# LCD_Disp_AIR.net
KiCad netlist of a schematic drawn in EAGLE
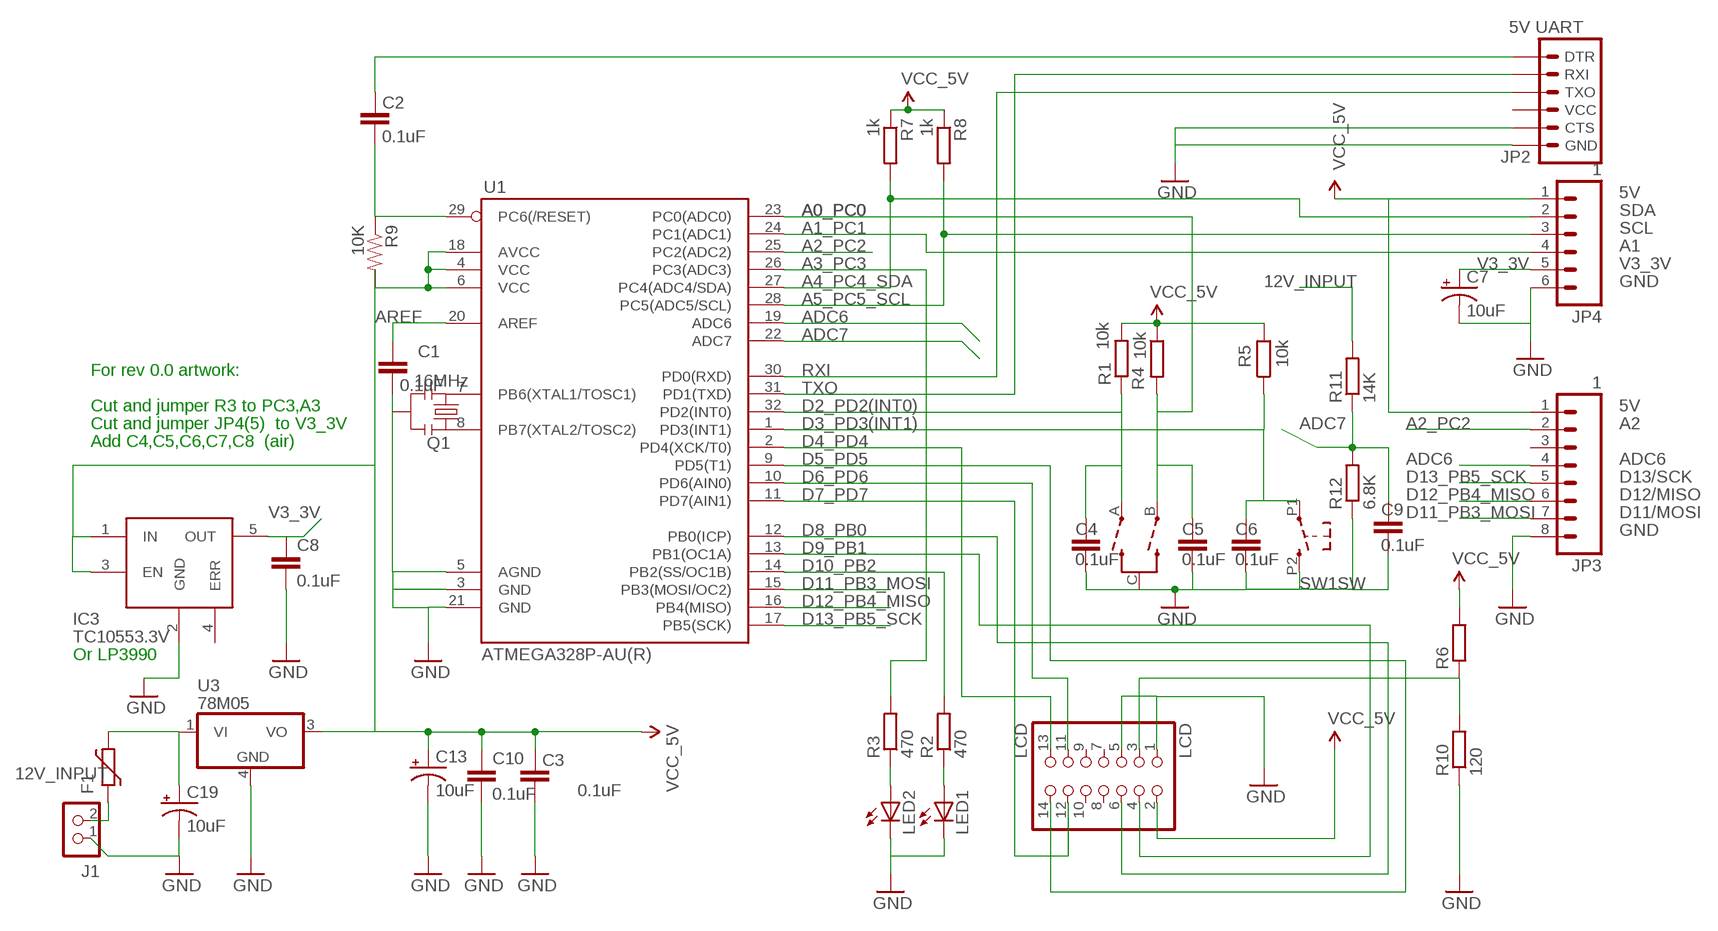
[diagram p0: schematic, sheet 1]

(export (version "E")
  (design (tool "Eeschema 10.0.6"))
  (components
    (comp (ref "C1")
      (value "0.1uF")
      (footprint "eagle-import:0805")
      (libsource (lib "eagle-import") (part "CAP0805"))
    )
    (comp (ref "C2")
      (value "0.1uF")
      (footprint "eagle-import:0805")
      (libsource (lib "eagle-import") (part "CAP0805"))
    )
    (comp (ref "C3")
      (value "0.1uF")
      (footprint "eagle-import:0805")
      (libsource (lib "eagle-import") (part "CAP0805"))
    )
    (comp (ref "C4")
      (value "0.1uF")
      (footprint "eagle-import:0805")
      (libsource (lib "eagle-import") (part "CAP0805"))
    )
    (comp (ref "C5")
      (value "0.1uF")
      (footprint "eagle-import:0805")
      (libsource (lib "eagle-import") (part "CAP0805"))
    )
    (comp (ref "C6")
      (value "0.1uF")
      (footprint "eagle-import:0805")
      (libsource (lib "eagle-import") (part "CAP0805"))
    )
    (comp (ref "C7")
      (value "10uF")
      (footprint "eagle-import:EIA3216")
      (libsource (lib "eagle-import") (part "CAP_POL1206"))
    )
    (comp (ref "C8")
      (value "0.1uF")
      (footprint "eagle-import:0805")
      (libsource (lib "eagle-import") (part "CAP0805"))
    )
    (comp (ref "C9")
      (value "0.1uF")
      (footprint "eagle-import:0805")
      (libsource (lib "eagle-import") (part "CAP0805"))
    )
    (comp (ref "C10")
      (value "0.1uF")
      (footprint "eagle-import:0805")
      (libsource (lib "eagle-import") (part "CAP0805"))
    )
    (comp (ref "C13")
      (value "10uF")
      (footprint "eagle-import:EIA3216")
      (libsource (lib "eagle-import") (part "CAP_POL1206"))
    )
    (comp (ref "C19")
      (value "10uF")
      (footprint "eagle-import:EIA7343")
      (libsource (lib "eagle-import") (part "CAP_POL7343"))
    )
    (comp (ref "F1")
      (value "FUSE_PTC-0805")
      (footprint "eagle-import:PTC0805")
      (libsource (lib "eagle-import") (part "FUSE_PTC-0805"))
    )
    (comp (ref "IC3")
      (value "TC10553.3V")
      (footprint "eagle-import:SOT23-5")
      (libsource (lib "eagle-import") (part "TC10553.3V"))
    )
    (comp (ref "J1")
      (value "12V input")
      (footprint "eagle-import:M1X2")
      (libsource (lib "eagle-import") (part "CON_HEADER_1X02-PTH"))
    )
    (comp (ref "JP2")
      (value "5V UART")
      (footprint "eagle-import:1X06")
      (libsource (lib "eagle-import") (part "ARDUINO_SERIAL_PROGRAMPTH"))
    )
    (comp (ref "JP3")
      (value "1")
      (footprint "eagle-import:1X08")
      (libsource (lib "eagle-import") (part "M081X08"))
    )
    (comp (ref "JP4")
      (value "1")
      (footprint "eagle-import:1X06")
      (libsource (lib "eagle-import") (part "M06SIP"))
    )
    (comp (ref "LCD")
      (value "LCD")
      (footprint "eagle-import:2X07")
      (libsource (lib "eagle-import") (part "PINHD-2X7"))
    )
    (comp (ref "LED1")
      (value "LED-5MM")
      (footprint "eagle-import:LED-5MM")
      (libsource (lib "eagle-import") (part "LED-5MM"))
    )
    (comp (ref "LED2")
      (value "LED-5MM")
      (footprint "eagle-import:LED-5MM")
      (libsource (lib "eagle-import") (part "LED-5MM"))
    )
    (comp (ref "Q1")
      (value "16MHz")
      (footprint "eagle-import:RESONATOR-SMD")
      (libsource (lib "eagle-import") (part "RESONATORSMD"))
    )
    (comp (ref "R1")
      (value "10k")
      (footprint "eagle-import:R603")
      (libsource (lib "eagle-import") (part "RESISTOR-0603"))
    )
    (comp (ref "R2")
      (value "470")
      (footprint "eagle-import:R603")
      (libsource (lib "eagle-import") (part "RESISTOR-0603"))
    )
    (comp (ref "R3")
      (value "470")
      (footprint "eagle-import:R603")
      (libsource (lib "eagle-import") (part "RESISTOR-0603"))
    )
    (comp (ref "R4")
      (value "10k")
      (footprint "eagle-import:R603")
      (libsource (lib "eagle-import") (part "RESISTOR-0603"))
    )
    (comp (ref "R5")
      (value "10k")
      (footprint "eagle-import:R603")
      (libsource (lib "eagle-import") (part "RESISTOR-0603"))
    )
    (comp (ref "R6")
      (value "RESISTOR-0603")
      (footprint "eagle-import:R603")
      (libsource (lib "eagle-import") (part "RESISTOR-0603"))
    )
    (comp (ref "R7")
      (value "1k")
      (footprint "eagle-import:R603")
      (libsource (lib "eagle-import") (part "RESISTOR-0603"))
    )
    (comp (ref "R8")
      (value "1k")
      (footprint "eagle-import:R603")
      (libsource (lib "eagle-import") (part "RESISTOR-0603"))
    )
    (comp (ref "R9")
      (value "10K")
      (footprint "eagle-import:0603")
      (libsource (lib "eagle-import") (part "RESISTOR0603"))
    )
    (comp (ref "R10")
      (value "120")
      (footprint "eagle-import:R603")
      (libsource (lib "eagle-import") (part "RESISTOR-0603"))
    )
    (comp (ref "R11")
      (value "14K")
      (footprint "eagle-import:R603")
      (libsource (lib "eagle-import") (part "RESISTOR-0603"))
    )
    (comp (ref "R12")
      (value "6.8K")
      (footprint "eagle-import:R603")
      (libsource (lib "eagle-import") (part "RESISTOR-0603"))
    )
    (comp (ref "SW1")
      (value "ENCODER_SW1-PEC12")
      (footprint "eagle-import:PEC12_INCREMENTAL_ENCODER")
      (libsource (lib "eagle-import") (part "ENCODER_SW1-PEC12"))
    )
    (comp (ref "U1")
      (value "ATMEGA328P-AU(R)")
      (footprint "eagle-import:TQFP32-08")
      (libsource (lib "eagle-import") (part "ATMEGA168"))
    )
    (comp (ref "U3")
      (value "78M05")
      (footprint "eagle-import:DPACK")
      (libsource (lib "eagle-import") (part "78MXXL"))
    )
  )
  (nets
    (net (code "1") (name "/12V_INPUT") (class "Default")
      (node (ref "C19") (pin "A") (pinfunction "+_A") (pintype "passive"))
      (node (ref "F1") (pin "2") (pinfunction "2_2") (pintype "passive"))
      (node (ref "R11") (pin "2") (pinfunction "2_2") (pintype "passive"))
      (node (ref "U3") (pin "1") (pinfunction "VI_1") (pintype "input"))
    )
    (net (code "2") (name "/A0_PC0") (class "Default")
      (node (ref "C5") (pin "2") (pinfunction "2_2") (pintype "passive"))
      (node (ref "R4") (pin "2") (pinfunction "2_2") (pintype "passive"))
      (node (ref "SW1") (pin "B") (pinfunction "B_B") (pintype "passive"))
      (node (ref "U1") (pin "23") (pinfunction "PC0(ADC0)_23") (pintype "bidirectional"))
    )
    (net (code "3") (name "/A1_PC1") (class "Default")
      (node (ref "JP4") (pin "4") (pinfunction "4_4") (pintype "passive"))
      (node (ref "U1") (pin "24") (pinfunction "PC1(ADC1)_24") (pintype "bidirectional"))
    )
    (net (code "4") (name "/A2_PC2") (class "Default")
      (node (ref "JP3") (pin "2") (pinfunction "2_2") (pintype "passive"))
      (node (ref "U1") (pin "25") (pinfunction "PC2(ADC2)_25") (pintype "bidirectional"))
    )
    (net (code "5") (name "/A3_PC3") (class "Default")
      (node (ref "R3") (pin "2") (pinfunction "2_2") (pintype "passive"))
      (node (ref "U1") (pin "26") (pinfunction "PC3(ADC3)_26") (pintype "bidirectional"))
    )
    (net (code "6") (name "/A4_PC4_SDA") (class "Default")
      (node (ref "JP4") (pin "2") (pinfunction "2_2") (pintype "passive"))
      (node (ref "R7") (pin "2") (pinfunction "2_2") (pintype "passive"))
      (node (ref "U1") (pin "27") (pinfunction "PC4(ADC4/SDA)_27") (pintype "bidirectional"))
    )
    (net (code "7") (name "/A5_PC5_SCL") (class "Default")
      (node (ref "JP4") (pin "3") (pinfunction "3_3") (pintype "passive"))
      (node (ref "R8") (pin "2") (pinfunction "2_2") (pintype "passive"))
      (node (ref "U1") (pin "28") (pinfunction "PC5(ADC5/SCL)_28") (pintype "bidirectional"))
    )
    (net (code "8") (name "/ADC6") (class "Default")
      (node (ref "JP3") (pin "4") (pinfunction "4_4") (pintype "passive"))
      (node (ref "U1") (pin "19") (pinfunction "ADC6_19") (pintype "bidirectional"))
    )
    (net (code "9") (name "/ADC7") (class "Default")
      (node (ref "C9") (pin "1") (pinfunction "1_1") (pintype "passive"))
      (node (ref "R11") (pin "1") (pinfunction "1_1") (pintype "passive"))
      (node (ref "R12") (pin "2") (pinfunction "2_2") (pintype "passive"))
      (node (ref "U1") (pin "22") (pinfunction "ADC7_22") (pintype "bidirectional"))
    )
    (net (code "10") (name "/AREF") (class "Default")
      (node (ref "C1") (pin "2") (pinfunction "2_2") (pintype "passive"))
      (node (ref "U1") (pin "20") (pinfunction "AREF_20") (pintype "bidirectional"))
    )
    (net (code "11") (name "/D2_PD2(INT0)") (class "Default")
      (node (ref "C4") (pin "2") (pinfunction "2_2") (pintype "passive"))
      (node (ref "R1") (pin "1") (pinfunction "1_1") (pintype "passive"))
      (node (ref "SW1") (pin "A") (pinfunction "A_A") (pintype "passive"))
      (node (ref "U1") (pin "32") (pinfunction "PD2(INT0)_32") (pintype "bidirectional"))
    )
    (net (code "12") (name "/D3_PD3(INT1)") (class "Default")
      (node (ref "C6") (pin "2") (pinfunction "2_2") (pintype "passive"))
      (node (ref "R5") (pin "1") (pinfunction "1_1") (pintype "passive"))
      (node (ref "SW1") (pin "P1") (pinfunction "1_P1") (pintype "passive"))
      (node (ref "U1") (pin "1") (pinfunction "PD3(INT1)_1") (pintype "bidirectional"))
    )
    (net (code "13") (name "/D4_PD4") (class "Default")
      (node (ref "LCD") (pin "13") (pinfunction "13_13") (pintype "passive"))
      (node (ref "U1") (pin "2") (pinfunction "PD4(XCK/T0)_2") (pintype "bidirectional"))
    )
    (net (code "14") (name "/D5_PD5") (class "Default")
      (node (ref "LCD") (pin "14") (pinfunction "14_14") (pintype "passive"))
      (node (ref "U1") (pin "9") (pinfunction "PD5(T1)_9") (pintype "bidirectional"))
    )
    (net (code "15") (name "/D6_PD6") (class "Default")
      (node (ref "LCD") (pin "11") (pinfunction "11_11") (pintype "passive"))
      (node (ref "U1") (pin "10") (pinfunction "PD6(AIN0)_10") (pintype "bidirectional"))
    )
    (net (code "16") (name "/D7_PD7") (class "Default")
      (node (ref "LCD") (pin "12") (pinfunction "12_12") (pintype "passive"))
      (node (ref "U1") (pin "11") (pinfunction "PD7(AIN1)_11") (pintype "bidirectional"))
    )
    (net (code "17") (name "/D8_PB0") (class "Default")
      (node (ref "LCD") (pin "6") (pinfunction "6_6") (pintype "passive"))
      (node (ref "U1") (pin "12") (pinfunction "PB0(ICP)_12") (pintype "bidirectional"))
    )
    (net (code "18") (name "/D9_PB1") (class "Default")
      (node (ref "LCD") (pin "4") (pinfunction "4_4") (pintype "passive"))
      (node (ref "U1") (pin "13") (pinfunction "PB1(OC1A)_13") (pintype "bidirectional"))
    )
    (net (code "19") (name "/D10_PB2") (class "Default")
      (node (ref "R2") (pin "2") (pinfunction "2_2") (pintype "passive"))
      (node (ref "U1") (pin "14") (pinfunction "PB2(SS/OC1B)_14") (pintype "bidirectional"))
    )
    (net (code "20") (name "/D11_PB3_MOSI") (class "Default")
      (node (ref "JP3") (pin "7") (pinfunction "7_7") (pintype "passive"))
      (node (ref "U1") (pin "15") (pinfunction "PB3(MOSI/OC2)_15") (pintype "bidirectional"))
    )
    (net (code "21") (name "/D12_PB4_MISO") (class "Default")
      (node (ref "JP3") (pin "6") (pinfunction "6_6") (pintype "passive"))
      (node (ref "U1") (pin "16") (pinfunction "PB4(MISO)_16") (pintype "bidirectional"))
    )
    (net (code "22") (name "/D13_PB5_SCK") (class "Default")
      (node (ref "JP3") (pin "5") (pinfunction "5_5") (pintype "passive"))
      (node (ref "U1") (pin "17") (pinfunction "PB5(SCK)_17") (pintype "bidirectional"))
    )
    (net (code "23") (name "/RXI") (class "Default")
      (node (ref "JP2") (pin "3") (pinfunction "TXO_3") (pintype "passive"))
      (node (ref "U1") (pin "30") (pinfunction "PD0(RXD)_30") (pintype "bidirectional"))
    )
    (net (code "24") (name "/TXO") (class "Default")
      (node (ref "JP2") (pin "2") (pinfunction "RXI_2") (pintype "passive"))
      (node (ref "U1") (pin "31") (pinfunction "PD1(TXD)_31") (pintype "bidirectional"))
    )
    (net (code "25") (name "/V3_3V") (class "Default")
      (node (ref "C7") (pin "A") (pinfunction "+_A") (pintype "passive"))
      (node (ref "C8") (pin "1") (pinfunction "1_1") (pintype "passive"))
      (node (ref "IC3") (pin "5") (pinfunction "OUT_5") (pintype "power_in"))
      (node (ref "JP4") (pin "5") (pinfunction "5_5") (pintype "passive"))
    )
    (net (code "26") (name "GND") (class "Default")
      (node (ref "C1") (pin "1") (pinfunction "1_1") (pintype "passive"))
      (node (ref "C10") (pin "2") (pinfunction "2_2") (pintype "passive"))
      (node (ref "C13") (pin "C") (pinfunction "-_C") (pintype "passive"))
      (node (ref "C19") (pin "C") (pinfunction "-_C") (pintype "passive"))
      (node (ref "C3") (pin "1") (pinfunction "1_1") (pintype "passive"))
      (node (ref "C4") (pin "1") (pinfunction "1_1") (pintype "passive"))
      (node (ref "C5") (pin "1") (pinfunction "1_1") (pintype "passive"))
      (node (ref "C6") (pin "1") (pinfunction "1_1") (pintype "passive"))
      (node (ref "C7") (pin "C") (pinfunction "-_C") (pintype "passive"))
      (node (ref "C8") (pin "2") (pinfunction "2_2") (pintype "passive"))
      (node (ref "C9") (pin "2") (pinfunction "2_2") (pintype "passive"))
      (node (ref "IC3") (pin "2") (pinfunction "GND_2") (pintype "power_in"))
      (node (ref "J1") (pin "1") (pinfunction "1_1") (pintype "passive"))
      (node (ref "JP2") (pin "5") (pinfunction "CTS_5") (pintype "passive"))
      (node (ref "JP2") (pin "6") (pinfunction "GND_6") (pintype "passive"))
      (node (ref "JP3") (pin "8") (pinfunction "8_8") (pintype "passive"))
      (node (ref "JP4") (pin "6") (pinfunction "6_6") (pintype "passive"))
      (node (ref "LCD") (pin "1") (pinfunction "1_1") (pintype "passive"))
      (node (ref "LCD") (pin "5") (pinfunction "5_5") (pintype "passive"))
      (node (ref "LED1") (pin "K") (pinfunction "C_K") (pintype "passive"))
      (node (ref "LED2") (pin "K") (pinfunction "C_K") (pintype "passive"))
      (node (ref "Q1") (pin "2") (pinfunction "2_2") (pintype "passive"))
      (node (ref "R10") (pin "1") (pinfunction "1_1") (pintype "passive"))
      (node (ref "R12") (pin "1") (pinfunction "1_1") (pintype "passive"))
      (node (ref "SW1") (pin "C") (pinfunction "C_C") (pintype "passive"))
      (node (ref "SW1") (pin "P2") (pinfunction "2_P2") (pintype "passive"))
      (node (ref "U1") (pin "21") (pinfunction "GND_21") (pintype "bidirectional"))
      (node (ref "U1") (pin "3") (pinfunction "GND_3") (pintype "bidirectional"))
      (node (ref "U1") (pin "5") (pinfunction "AGND_5") (pintype "bidirectional"))
      (node (ref "U3") (pin "4") (pinfunction "GND_4") (pintype "passive"))
    )
    (net (code "27") (name "Net-(F1-Pad1)") (class "Default")
      (node (ref "F1") (pin "1") (pinfunction "1_1") (pintype "passive"))
      (node (ref "J1") (pin "2") (pinfunction "2_2") (pintype "passive"))
    )
    (net (code "28") (name "Net-(JP2-DTR)") (class "Default")
      (node (ref "C2") (pin "2") (pinfunction "2_2") (pintype "passive"))
      (node (ref "JP2") (pin "1") (pinfunction "DTR_1") (pintype "passive"))
    )
    (net (code "29") (name "Net-(LCD-Pad3)") (class "Default")
      (node (ref "LCD") (pin "3") (pinfunction "3_3") (pintype "passive"))
      (node (ref "R10") (pin "2") (pinfunction "2_2") (pintype "passive"))
      (node (ref "R6") (pin "1") (pinfunction "1_1") (pintype "passive"))
    )
    (net (code "30") (name "Net-(LED1-PadA)") (class "Default")
      (node (ref "LED1") (pin "A") (pinfunction "A_A") (pintype "passive"))
      (node (ref "R2") (pin "1") (pinfunction "1_1") (pintype "passive"))
    )
    (net (code "31") (name "Net-(LED2-PadA)") (class "Default")
      (node (ref "LED2") (pin "A") (pinfunction "A_A") (pintype "passive"))
      (node (ref "R3") (pin "1") (pinfunction "1_1") (pintype "passive"))
    )
    (net (code "32") (name "Net-(U1-PB6(XTAL1{slash}TOSC1))") (class "Default")
      (node (ref "Q1") (pin "3") (pinfunction "3_3") (pintype "passive"))
      (node (ref "U1") (pin "7") (pinfunction "PB6(XTAL1/TOSC1)_7") (pintype "bidirectional"))
    )
    (net (code "33") (name "Net-(U1-PB7(XTAL2{slash}TOSC2))") (class "Default")
      (node (ref "Q1") (pin "1") (pinfunction "1_1") (pintype "passive"))
      (node (ref "U1") (pin "8") (pinfunction "PB7(XTAL2/TOSC2)_8") (pintype "bidirectional"))
    )
    (net (code "34") (name "Net-(U1-PC6({slash}RESET))") (class "Default")
      (node (ref "C2") (pin "1") (pinfunction "1_1") (pintype "passive"))
      (node (ref "R9") (pin "1") (pinfunction "1_1") (pintype "passive"))
      (node (ref "U1") (pin "29") (pinfunction "PC6(/RESET)_29") (pintype "bidirectional"))
    )
    (net (code "35") (name "VCC_5V") (class "Default")
      (node (ref "C10") (pin "1") (pinfunction "1_1") (pintype "passive"))
      (node (ref "C13") (pin "A") (pinfunction "+_A") (pintype "passive"))
      (node (ref "C3") (pin "2") (pinfunction "2_2") (pintype "passive"))
      (node (ref "IC3") (pin "1") (pinfunction "IN_1") (pintype "power_in"))
      (node (ref "IC3") (pin "3") (pinfunction "EN_3") (pintype "input"))
      (node (ref "JP3") (pin "1") (pinfunction "1_1") (pintype "passive"))
      (node (ref "JP4") (pin "1") (pinfunction "1_1") (pintype "passive"))
      (node (ref "LCD") (pin "2") (pinfunction "2_2") (pintype "passive"))
      (node (ref "R1") (pin "2") (pinfunction "2_2") (pintype "passive"))
      (node (ref "R4") (pin "1") (pinfunction "1_1") (pintype "passive"))
      (node (ref "R5") (pin "2") (pinfunction "2_2") (pintype "passive"))
      (node (ref "R6") (pin "2") (pinfunction "2_2") (pintype "passive"))
      (node (ref "R7") (pin "1") (pinfunction "1_1") (pintype "passive"))
      (node (ref "R8") (pin "1") (pinfunction "1_1") (pintype "passive"))
      (node (ref "R9") (pin "2") (pinfunction "2_2") (pintype "passive"))
      (node (ref "U1") (pin "18") (pinfunction "AVCC_18") (pintype "bidirectional"))
      (node (ref "U1") (pin "4") (pinfunction "VCC_4") (pintype "bidirectional"))
      (node (ref "U1") (pin "6") (pinfunction "VCC_6") (pintype "bidirectional"))
      (node (ref "U3") (pin "3") (pinfunction "VO_3") (pintype "passive"))
    )
    (net (code "36") (name "unconnected-(IC3-ERR-Pad4)") (class "Default")
      (node (ref "IC3") (pin "4") (pinfunction "ERR_4") (pintype "output"))
    )
    (net (code "37") (name "unconnected-(JP2-VCC-Pad4)") (class "Default")
      (node (ref "JP2") (pin "4") (pinfunction "VCC_4") (pintype "passive"))
    )
    (net (code "38") (name "unconnected-(JP3-Pad3)") (class "Default")
      (node (ref "JP3") (pin "3") (pinfunction "3_3") (pintype "passive"))
    )
    (net (code "39") (name "unconnected-(LCD-Pad7)") (class "Default")
      (node (ref "LCD") (pin "7") (pinfunction "7_7") (pintype "passive"))
    )
    (net (code "40") (name "unconnected-(LCD-Pad8)") (class "Default")
      (node (ref "LCD") (pin "8") (pinfunction "8_8") (pintype "passive"))
    )
    (net (code "41") (name "unconnected-(LCD-Pad9)") (class "Default")
      (node (ref "LCD") (pin "9") (pinfunction "9_9") (pintype "passive"))
    )
    (net (code "42") (name "unconnected-(LCD-Pad10)") (class "Default")
      (node (ref "LCD") (pin "10") (pinfunction "10_10") (pintype "passive"))
    )
  )
)
